# 1-Schematic_SillyILO-0_0_1.net
KiCad netlist of a schematic drawn in EasyEDA
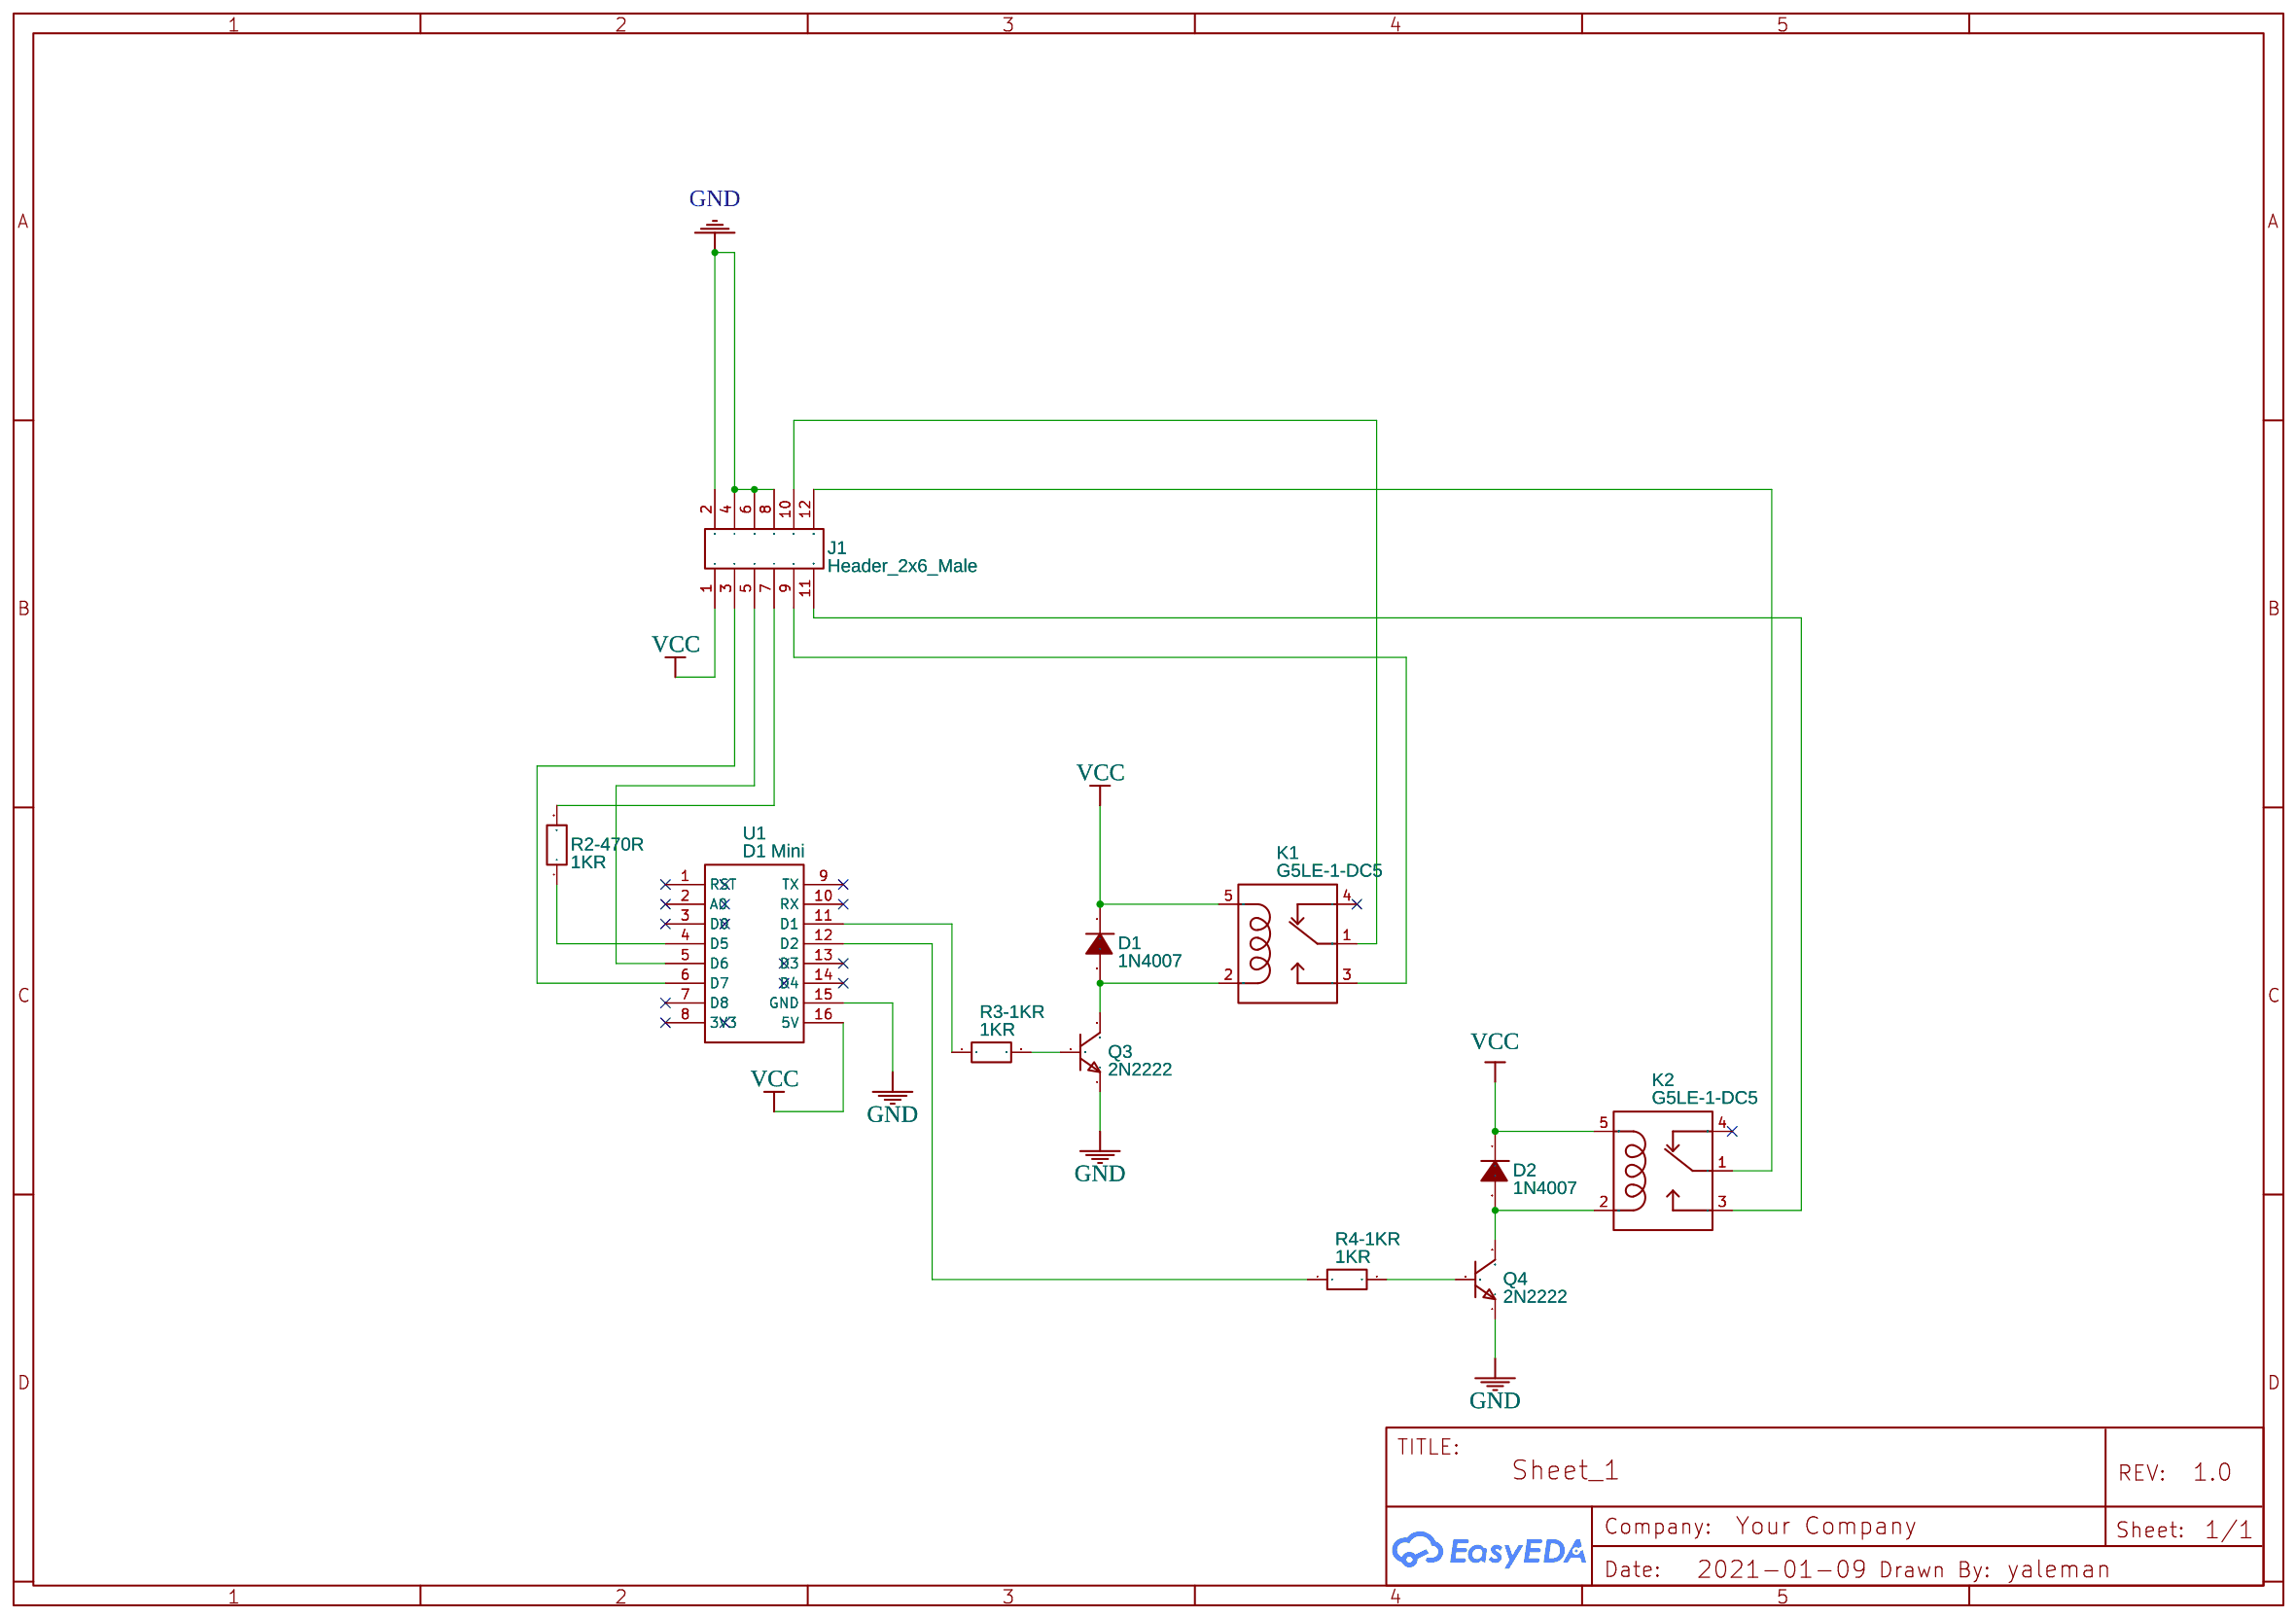
[diagram p0: schematic sheet]

(export (version "E")
  (design (tool "Eeschema 10.0.6"))
  (components
    (comp (ref "D1")
      (value "1N4007")
      (fields (field (name "BOM_Supplier Part") "C106903"))
      (libsource (lib "") (part "1N4007"))
    )
    (comp (ref "D2")
      (value "1N4007")
      (fields (field (name "BOM_Supplier Part") "C106903"))
      (libsource (lib "") (part "1N4007"))
    )
    (comp (ref "J1") (value "Header_2x6_Male") (libsource (lib "") (part "Header_2x6_Male")))
    (comp (ref "K1")
      (value "G5LE-1-DC5")
      (fields (field (name "BOM_Supplier Part") "C152704"))
      (libsource (lib "") (part "G5LE-1-DC5"))
    )
    (comp (ref "K2")
      (value "G5LE-1-DC5")
      (fields (field (name "BOM_Supplier Part") "C152704"))
      (libsource (lib "") (part "G5LE-1-DC5"))
    )
    (comp (ref "Q3")
      (value "2N2222")
      (fields (field (name "BOM_Supplier Part") "C118536"))
      (libsource (lib "") (part "2N2222"))
    )
    (comp (ref "Q4")
      (value "2N2222")
      (fields (field (name "BOM_Supplier Part") "C118536"))
      (libsource (lib "") (part "2N2222"))
    )
    (comp (ref "R2-470R")
      (value "1KR")
      (fields
        (field (name "BOM_Manufacturer Part") "MF1/4DCT26A1001F")
        (field (name "BOM_Supplier Part") "660-MF1/4DCT26A1001F")
      )
      (libsource (lib "") (part "1KR"))
    )
    (comp (ref "R3-1KR")
      (value "1KR")
      (fields
        (field (name "BOM_Manufacturer Part") "MF1/4DCT26A1001F")
        (field (name "BOM_Supplier Part") "660-MF1/4DCT26A1001F")
      )
      (libsource (lib "") (part "1KR_2"))
    )
    (comp (ref "R4-1KR")
      (value "1KR")
      (fields
        (field (name "BOM_Manufacturer Part") "MF1/4DCT26A1001F")
        (field (name "BOM_Supplier Part") "660-MF1/4DCT26A1001F")
      )
      (libsource (lib "") (part "1KR_1"))
    )
    (comp (ref "U1") (value "D1 Mini") (libsource (lib "") (part "D1 Mini")))
  )
  (nets
    (net (code "1") (name "GND") (class "Default")
      (node (ref "J1") (pin "2") (pinfunction "2_2") (pintype "unspecified"))
      (node (ref "J1") (pin "4") (pinfunction "4_4") (pintype "unspecified"))
      (node (ref "J1") (pin "6") (pinfunction "6_6") (pintype "unspecified"))
      (node (ref "J1") (pin "8") (pinfunction "8_8") (pintype "unspecified"))
      (node (ref "Q3") (pin "1") (pinfunction "E_1") (pintype "unspecified"))
      (node (ref "Q4") (pin "1") (pinfunction "E_1") (pintype "unspecified"))
      (node (ref "U1") (pin "15") (pinfunction "GND_15") (pintype "passive"))
    )
    (net (code "2") (name "Net-(D1-A)") (class "Default")
      (node (ref "D1") (pin "2") (pinfunction "A_2") (pintype "unspecified"))
      (node (ref "K1") (pin "2") (pinfunction "COIL2_2") (pintype "unspecified"))
      (node (ref "Q3") (pin "3") (pinfunction "C_3") (pintype "unspecified"))
    )
    (net (code "3") (name "Net-(D2-A)") (class "Default")
      (node (ref "D2") (pin "2") (pinfunction "A_2") (pintype "unspecified"))
      (node (ref "K2") (pin "2") (pinfunction "COIL2_2") (pintype "unspecified"))
      (node (ref "Q4") (pin "3") (pinfunction "C_3") (pintype "unspecified"))
    )
    (net (code "4") (name "Net-(J1-Pad7)") (class "Default")
      (node (ref "J1") (pin "7") (pinfunction "7_7") (pintype "unspecified"))
      (node (ref "R2-470R") (pin "2") (pinfunction "2_2") (pintype "unspecified"))
    )
    (net (code "5") (name "Net-(K1-C)") (class "Default")
      (node (ref "J1") (pin "10") (pinfunction "10_10") (pintype "unspecified"))
      (node (ref "K1") (pin "1") (pinfunction "C_1") (pintype "unspecified"))
    )
    (net (code "6") (name "Net-(K1-NO)") (class "Default")
      (node (ref "J1") (pin "9") (pinfunction "9_9") (pintype "unspecified"))
      (node (ref "K1") (pin "3") (pinfunction "NO_3") (pintype "unspecified"))
    )
    (net (code "7") (name "Net-(K2-C)") (class "Default")
      (node (ref "J1") (pin "12") (pinfunction "12_12") (pintype "unspecified"))
      (node (ref "K2") (pin "1") (pinfunction "C_1") (pintype "unspecified"))
    )
    (net (code "8") (name "Net-(K2-NO)") (class "Default")
      (node (ref "J1") (pin "11") (pinfunction "11_11") (pintype "unspecified"))
      (node (ref "K2") (pin "3") (pinfunction "NO_3") (pintype "unspecified"))
    )
    (net (code "9") (name "Net-(Q3-B)") (class "Default")
      (node (ref "Q3") (pin "2") (pinfunction "B_2") (pintype "unspecified"))
      (node (ref "R3-1KR") (pin "2") (pinfunction "2_2") (pintype "unspecified"))
    )
    (net (code "10") (name "Net-(Q4-B)") (class "Default")
      (node (ref "Q4") (pin "2") (pinfunction "B_2") (pintype "unspecified"))
      (node (ref "R4-1KR") (pin "2") (pinfunction "2_2") (pintype "unspecified"))
    )
    (net (code "11") (name "Net-(U1-D1)") (class "Default")
      (node (ref "R3-1KR") (pin "1") (pinfunction "1_1") (pintype "unspecified"))
      (node (ref "U1") (pin "11") (pinfunction "D1_11") (pintype "bidirectional"))
    )
    (net (code "12") (name "Net-(U1-D2)") (class "Default")
      (node (ref "R4-1KR") (pin "1") (pinfunction "1_1") (pintype "unspecified"))
      (node (ref "U1") (pin "12") (pinfunction "D2_12") (pintype "bidirectional"))
    )
    (net (code "13") (name "Net-(U1-D5)") (class "Default")
      (node (ref "R2-470R") (pin "1") (pinfunction "1_1") (pintype "unspecified"))
      (node (ref "U1") (pin "4") (pinfunction "D5_4") (pintype "bidirectional"))
    )
    (net (code "14") (name "Net-(U1-D6)") (class "Default")
      (node (ref "J1") (pin "5") (pinfunction "5_5") (pintype "unspecified"))
      (node (ref "U1") (pin "5") (pinfunction "D6_5") (pintype "bidirectional"))
    )
    (net (code "15") (name "Net-(U1-D7)") (class "Default")
      (node (ref "J1") (pin "3") (pinfunction "3_3") (pintype "unspecified"))
      (node (ref "U1") (pin "6") (pinfunction "D7_6") (pintype "bidirectional"))
    )
    (net (code "16") (name "VCC") (class "Default")
      (node (ref "D1") (pin "1") (pinfunction "K_1") (pintype "unspecified"))
      (node (ref "D2") (pin "1") (pinfunction "K_1") (pintype "unspecified"))
      (node (ref "J1") (pin "1") (pinfunction "1_1") (pintype "unspecified"))
      (node (ref "K1") (pin "5") (pinfunction "COIL1_5") (pintype "unspecified"))
      (node (ref "K2") (pin "5") (pinfunction "COIL1_5") (pintype "unspecified"))
      (node (ref "U1") (pin "16") (pinfunction "5V_16") (pintype "passive"))
    )
    (net (code "17") (name "unconnected-(K1-NC-Pad4)") (class "Default")
      (node (ref "K1") (pin "4") (pinfunction "NC_4") (pintype "unspecified+no_connect"))
    )
    (net (code "18") (name "unconnected-(K2-NC-Pad4)") (class "Default")
      (node (ref "K2") (pin "4") (pinfunction "NC_4") (pintype "unspecified+no_connect"))
    )
    (net (code "19") (name "unconnected-(U1-3V3-Pad8)") (class "Default")
      (node (ref "U1") (pin "8") (pinfunction "3V3_8") (pintype "passive+no_connect"))
    )
    (net (code "20") (name "unconnected-(U1-A0-Pad2)") (class "Default")
      (node (ref "U1") (pin "2") (pinfunction "A0_2") (pintype "bidirectional+no_connect"))
    )
    (net (code "21") (name "unconnected-(U1-D0-Pad3)") (class "Default")
      (node (ref "U1") (pin "3") (pinfunction "D0_3") (pintype "bidirectional+no_connect"))
    )
    (net (code "22") (name "unconnected-(U1-D3-Pad13)") (class "Default")
      (node (ref "U1") (pin "13") (pinfunction "D3_13") (pintype "bidirectional+no_connect"))
    )
    (net (code "23") (name "unconnected-(U1-D4-Pad14)") (class "Default")
      (node (ref "U1") (pin "14") (pinfunction "D4_14") (pintype "bidirectional+no_connect"))
    )
    (net (code "24") (name "unconnected-(U1-D8-Pad7)") (class "Default")
      (node (ref "U1") (pin "7") (pinfunction "D8_7") (pintype "bidirectional+no_connect"))
    )
    (net (code "25") (name "unconnected-(U1-RST-Pad1)") (class "Default")
      (node (ref "U1") (pin "1") (pinfunction "RST_1") (pintype "input+no_connect"))
    )
    (net (code "26") (name "unconnected-(U1-RX-Pad10)") (class "Default")
      (node (ref "U1") (pin "10") (pinfunction "RX_10") (pintype "bidirectional+no_connect"))
    )
    (net (code "27") (name "unconnected-(U1-TX-Pad9)") (class "Default")
      (node (ref "U1") (pin "9") (pinfunction "TX_9") (pintype "bidirectional+no_connect"))
    )
  )
)
